# DAC.net
KiCad netlist of a schematic drawn in Altium Designer
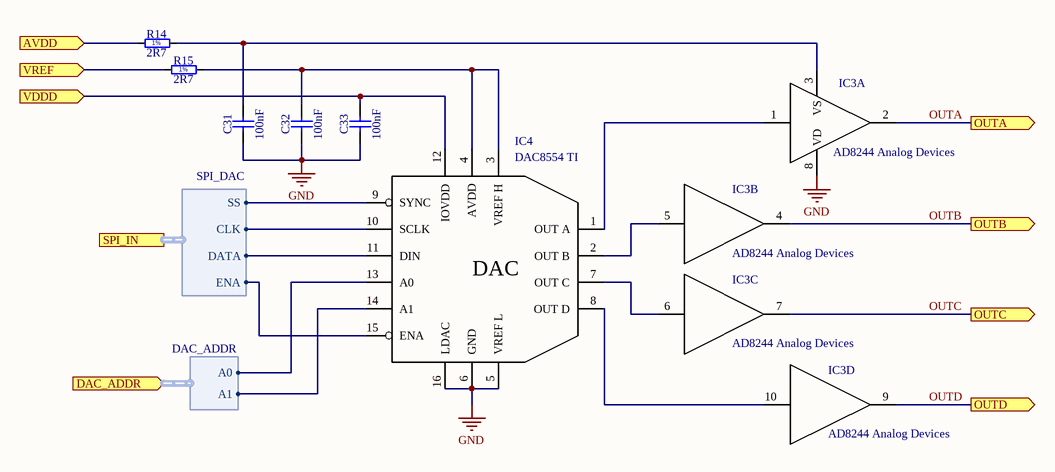
[diagram p0: DAC.SchDoc]

(export (version "E")
  (design (tool "Eeschema 10.0.6"))
  (components
    (comp (ref "C31")
      (value "100nF")
      (footprint "CAPC2012X135N")
      (description "Non-polarised capacitor")
      (fields
        (field (name "PART NUMBER") "CC0805_100NF_50V_10%_X7R")
        (field (name "VOLTAGE") "50V")
        (field (name "AUTHOR") "CERN DEM JLC")
      )
      (libsource (lib "Capacitors") (part "Capacitor - non polarized"))
    )
    (comp (ref "C32")
      (value "100nF")
      (footprint "CAPC2012X135N")
      (description "Non-polarised capacitor")
      (fields
        (field (name "PART NUMBER") "CC0805_100NF_50V_10%_X7R")
        (field (name "VOLTAGE") "50V")
        (field (name "AUTHOR") "CERN DEM JLC")
      )
      (libsource (lib "Capacitors") (part "Capacitor - non polarized"))
    )
    (comp (ref "C33")
      (value "100nF")
      (footprint "CAPC2012X135N")
      (description "Non-polarised capacitor")
      (fields
        (field (name "PART NUMBER") "CC0805_100NF_50V_10%_X7R")
        (field (name "VOLTAGE") "50V")
        (field (name "AUTHOR") "CERN DEM JLC")
      )
      (libsource (lib "Capacitors") (part "Capacitor - non polarized"))
    )
    (comp (ref "IC3")
      (value "AD8244 Analog Devices")
      (footprint "TSSOP50P490X110-10N")
      (fields (field (name "MANUFACTURER") "Analog Devices"))
      (libsource (lib "Additional") (part "AD8244"))
    )
    (comp (ref "IC4")
      (value "DAC8554 TI")
      (footprint "TSOP65P640X120-16N")
      (fields (field (name "MANUFACTURER") "TI"))
      (libsource (lib "Additional") (part "DAC8554"))
    )
    (comp (ref "R14")
      (value "2R7")
      (footprint "RESC2012X60N")
      (description "Resistor - 1%")
      (fields
        (field (name "PART NUMBER") "R0805_2R7_1%_0.125W_200PPM")
        (field (name "POWER") "0.125W")
        (field (name "AUTHOR") "CERN DEM JLC")
      )
      (libsource (lib "Resistors") (part "Resistor - 1%"))
    )
    (comp (ref "R15")
      (value "2R7")
      (footprint "RESC2012X60N")
      (description "Resistor - 1%")
      (fields
        (field (name "PART NUMBER") "R0805_2R7_1%_0.125W_200PPM")
        (field (name "POWER") "0.125W")
        (field (name "AUTHOR") "CERN DEM JLC")
      )
      (libsource (lib "Resistors") (part "Resistor - 1%"))
    )
  )
  (nets
    (net (code "3") (name "/A0") (class "Default")
      (node (ref "IC4") (pin "13") (pinfunction "A0_13") (pintype "passive"))
    )
    (net (code "4") (name "/A1") (class "Default")
      (node (ref "IC4") (pin "14") (pinfunction "A1_14") (pintype "passive"))
    )
    (net (code "5") (name "/AVDD") (class "Default")
      (node (ref "R14") (pin "1") (pinfunction "1_1") (pintype "passive"))
    )
    (net (code "6") (name "/CLK") (class "Default")
      (node (ref "IC4") (pin "10") (pinfunction "SCLK_10") (pintype "passive"))
    )
    (net (code "7") (name "/DATA") (class "Default")
      (node (ref "IC4") (pin "11") (pinfunction "DIN_11") (pintype "passive"))
    )
    (net (code "8") (name "/ENA") (class "Default")
      (node (ref "IC4") (pin "15") (pinfunction "ENA_15") (pintype "passive"))
    )
    (net (code "9") (name "/OUTA") (class "Default")
      (node (ref "IC3") (pin "2") (pinfunction "OUT_A_2") (pintype "passive"))
    )
    (net (code "10") (name "/OUTB") (class "Default")
      (node (ref "IC3") (pin "4") (pinfunction "OUT_B_4") (pintype "passive"))
    )
    (net (code "11") (name "/OUTC") (class "Default")
      (node (ref "IC3") (pin "7") (pinfunction "OUT_C_7") (pintype "passive"))
    )
    (net (code "12") (name "/OUTD") (class "Default")
      (node (ref "IC3") (pin "9") (pinfunction "OUT_D_9") (pintype "passive"))
    )
    (net (code "13") (name "/SS") (class "Default")
      (node (ref "IC4") (pin "9") (pinfunction "SYNC_9") (pintype "passive"))
    )
    (net (code "14") (name "/VDDD") (class "Default")
      (node (ref "C33") (pin "2") (pinfunction "2_2") (pintype "passive"))
      (node (ref "IC4") (pin "12") (pinfunction "IOVDD_12") (pintype "passive"))
    )
    (net (code "15") (name "/VREF") (class "Default")
      (node (ref "R15") (pin "1") (pinfunction "1_1") (pintype "passive"))
    )
    (net (code "18") (name "GND") (class "Default")
      (node (ref "C31") (pin "1") (pinfunction "1_1") (pintype "passive"))
      (node (ref "C32") (pin "1") (pinfunction "1_1") (pintype "passive"))
      (node (ref "C33") (pin "1") (pinfunction "1_1") (pintype "passive"))
      (node (ref "IC3") (pin "8") (pinfunction "VD_8") (pintype "passive"))
      (node (ref "IC4") (pin "16") (pinfunction "LDAC_16") (pintype "passive"))
      (node (ref "IC4") (pin "5") (pinfunction "VREF_L_5") (pintype "passive"))
      (node (ref "IC4") (pin "6") (pinfunction "GND_6") (pintype "passive"))
    )
    (net (code "19") (name "Net-(IC3A-IN_A)") (class "Default")
      (node (ref "IC3") (pin "1") (pinfunction "IN_A_1") (pintype "passive"))
      (node (ref "IC4") (pin "1") (pinfunction "OUT_A_1") (pintype "passive"))
    )
    (net (code "20") (name "Net-(IC3A-VS)") (class "Default")
      (node (ref "C31") (pin "2") (pinfunction "2_2") (pintype "passive"))
      (node (ref "IC3") (pin "3") (pinfunction "VS_3") (pintype "passive"))
      (node (ref "R14") (pin "2") (pinfunction "2_2") (pintype "passive"))
    )
    (net (code "21") (name "Net-(IC3B-IN_B)") (class "Default")
      (node (ref "IC3") (pin "5") (pinfunction "IN_B_5") (pintype "passive"))
      (node (ref "IC4") (pin "2") (pinfunction "OUT_B_2") (pintype "passive"))
    )
    (net (code "22") (name "Net-(IC3C-IN_C)") (class "Default")
      (node (ref "IC3") (pin "6") (pinfunction "IN_C_6") (pintype "passive"))
      (node (ref "IC4") (pin "7") (pinfunction "OUT_C_7") (pintype "passive"))
    )
    (net (code "23") (name "Net-(IC3D-IN_D)") (class "Default")
      (node (ref "IC3") (pin "10") (pinfunction "IN_D_10") (pintype "passive"))
      (node (ref "IC4") (pin "8") (pinfunction "OUT_D_8") (pintype "passive"))
    )
    (net (code "24") (name "Net-(IC4-AVDD)") (class "Default")
      (node (ref "C32") (pin "2") (pinfunction "2_2") (pintype "passive"))
      (node (ref "IC4") (pin "3") (pinfunction "VREF_H_3") (pintype "passive"))
      (node (ref "IC4") (pin "4") (pinfunction "AVDD_4") (pintype "passive"))
      (node (ref "R15") (pin "2") (pinfunction "2_2") (pintype "passive"))
    )
  )
)
